# Power_Supply_and_Connector.net
KiCad netlist of a schematic drawn in Altium Designer
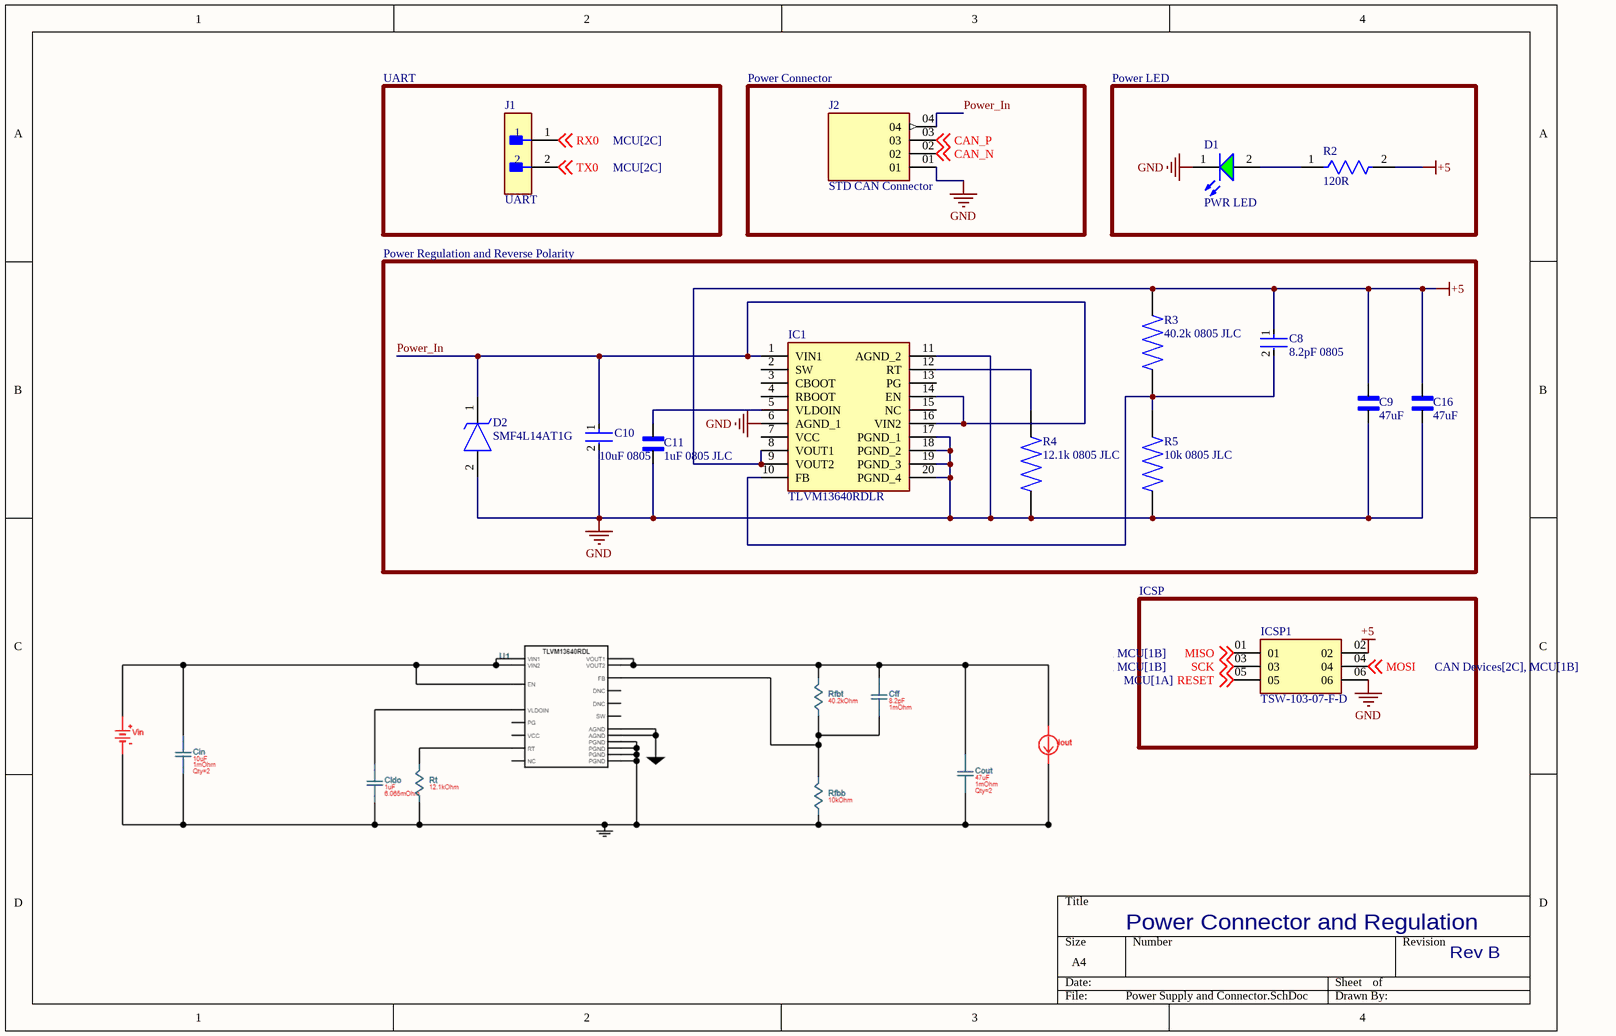
[diagram p0: Power Supply and Connector.SchDoc]

(export (version "E")
  (design (tool "Eeschema 10.0.6"))
  (components
    (comp (ref "C8")
      (value "8.2pF 0805")
      (footprint "FP-GQM219-0_15-IPC_C")
      (description "Ceramic Capacitor 8.2pF ±0.25pF 250VDC C0G 0805 Paper T/R")
      (libsource (lib "Altium Content Vault") (part "b4654b650e69147ec39a6b967a45e02"))
    )
    (comp (ref "C9")
      (value "47uF")
      (footprint "GRM31CR61E476ME44K:CAPC3216X160N")
      (fields
        (field (name "MF") "{'manufacturer': u'Murata Electronics'}")
        (field (name "MP") "GRM31CR61E476ME44K")
      )
      (libsource (lib "*") (part "GRM31CR61E476ME44K"))
    )
    (comp (ref "C10")
      (value "10uF 0805")
      (footprint "FP-GRM21B-0_2-e0_2_0_7-IPC_A")
      (description "Chip Multilayer Ceramic Capacitors for General Purpose, 0805, 10uF, X5R, 15%, 10%, 50V")
      (fields (field (name "TOLERANCE") "10%"))
      (libsource (lib "Altium Content Vault") (part "b4654b650e69147ec39a6b967a45e02"))
    )
    (comp (ref "C11")
      (value "1uF 0805 JLC")
      (footprint "CL21B105KBFNNNE:CAPC2012X140N")
      (description "Capacitor: ceramic; MLCC; 1uF; 50V; X7R; Â±10%; SMD; 0805")
      (fields
        (field (name "MF") "{'manufacturer': u'Samsung Electro-Mechanics'}")
        (field (name "MP") "CL21B105KBFNNNE")
      )
      (libsource (lib "*") (part "CL21B105KBFNNNE"))
    )
    (comp (ref "C16")
      (value "47uF")
      (footprint "GRM31CR61E476ME44K:CAPC3216X160N")
      (fields
        (field (name "MF") "{'manufacturer': u'Murata Electronics'}")
        (field (name "MP") "GRM31CR61E476ME44K")
      )
      (libsource (lib "*") (part "GRM31CR61E476ME44K"))
    )
    (comp (ref "D1")
      (value "PWR LED")
      (footprint "WL-SMCW_0805_150080xx75000")
      (description "WURTH ELEKTRONIK - 150080GS75000 - LED, Green, SMD, 0805, 30 mA, 3.2 V, 520 nm")
      (libsource (lib "Altium Content Vault") (part "LED_Green_2A-1K"))
    )
    (comp (ref "D2")
      (value "SMF4L14AT1G")
      (footprint "SamacSys:SODFL3619X98N")
      (description "TVS Diode (Uni-directional)")
      (fields (field (name "MOUSER PART NUMBER") "576-SMF4L14AT1G"))
      (libsource (lib "*") (part "SMF4L14AT1G"))
    )
    (comp (ref "IC1")
      (value "TLVM13640RDLR")
      (footprint "SamacSys:TLVM13640RDLR")
      (description "Integrated Circuit")
      (fields (field (name "MOUSER PART NUMBER") "595-TLVM13640RDLR"))
      (libsource (lib "*") (part "TLVM13640RDLR"))
    )
    (comp (ref "ICSP1")
      (value "TSW-103-07-F-D")
      (footprint "TSW-103-07-F-D:SAMTEC_TSW-103-07-F-D")
      (fields (field (name "MF") "{'manufacturer': u'Samtec'}"))
      (libsource (lib "*") (part "TSW-103-07-F-D"))
    )
    (comp (ref "J1")
      (value "UART")
      (footprint "FP-TSW-102-07-F-S-MFG")
      (description "CONN HEADER VERT 2POS 2.54MM")
      (libsource (lib "Altium Content Vault") (part "3bc925449376181038e59eaffc5286c"))
    )
    (comp (ref "J2")
      (value "STD CAN Connector")
      (footprint "TSW-104-07-F-S:SAMTEC_TSW-104-07-F-S")
      (fields (field (name "MF") "{'manufacturer': u'Samtec'}") (field (name "MP") "TSW-104-07-F-S"))
      (libsource (lib "*") (part "TSW-104-07-F-S"))
    )
    (comp (ref "R2")
      (value "120R")
      (footprint "FP-CRCW0805-e3-IPC_C")
      (description "RES Thick Film, 120Ω, 1%, 0.125W, 100ppm/°C, 0805")
      (fields (field (name "TOLERANCE") "1%"))
      (libsource (lib "Altium Content Vault") (part "1029c3af85768c4190bb7ad29bc67b5"))
    )
    (comp (ref "R3")
      (value "40.2k 0805 JLC")
      (footprint "0805W8F4022T5E:RESC2012X65N")
      (fields (field (name "MF") "{'manufacturer': u'Uni-Royal'}") (field (name "MP") "0805W8F4022T5E"))
      (libsource (lib "*") (part "0805W8F4022T5E"))
    )
    (comp (ref "R4")
      (value "12.1k 0805 JLC")
      (footprint "0805W8F1212T5E:RESC2012X65N")
      (fields (field (name "MF") "{'manufacturer': u'Uni-Royal'}") (field (name "MP") "0805W8F1212T5E"))
      (libsource (lib "*") (part "0805W8F1212T5E"))
    )
    (comp (ref "R5")
      (value "10k 0805 JLC")
      (footprint "0805W8F1002T5E:RESC2012X65N")
      (fields (field (name "MF") "{'manufacturer': u'Uni-Royal'}") (field (name "MP") "0805W8F1002T5E"))
      (libsource (lib "*") (part "0805W8F1002T5E"))
    )
  )
  (nets
    (net (code "1") (name "+5") (class "Default")
      (node (ref "C16") (pin "2") (pinfunction "2_2") (pintype "passive"))
      (node (ref "C8") (pin "1") (pinfunction "1_1") (pintype "passive"))
      (node (ref "C9") (pin "2") (pinfunction "2_2") (pintype "passive"))
      (node (ref "IC1") (pin "8") (pinfunction "VOUT1_8") (pintype "passive"))
      (node (ref "IC1") (pin "9") (pinfunction "VOUT2_9") (pintype "passive"))
      (node (ref "ICSP1") (pin "02") (pinfunction "02_02") (pintype "passive"))
      (node (ref "R2") (pin "2") (pinfunction "2_2") (pintype "passive"))
      (node (ref "R3") (pin "2") (pinfunction "2_2") (pintype "passive"))
    )
    (net (code "2") (name "/Power_In") (class "Default")
      (node (ref "C10") (pin "1") (pinfunction "1_1") (pintype "passive"))
      (node (ref "D2") (pin "1") (pinfunction "K_1") (pintype "passive"))
      (node (ref "IC1") (pin "1") (pinfunction "VIN1_1") (pintype "passive"))
      (node (ref "IC1") (pin "14") (pinfunction "EN_14") (pintype "passive"))
      (node (ref "IC1") (pin "16") (pinfunction "VIN2_16") (pintype "passive"))
      (node (ref "J2") (pin "04") (pinfunction "04_04") (pintype "output"))
    )
    (net (code "3") (name "CAN_N") (class "Default")
      (node (ref "J2") (pin "02") (pinfunction "02_02") (pintype "passive"))
    )
    (net (code "4") (name "CAN_P") (class "Default")
      (node (ref "J2") (pin "03") (pinfunction "03_03") (pintype "passive"))
    )
    (net (code "5") (name "GND") (class "Default")
      (node (ref "C10") (pin "2") (pinfunction "2_2") (pintype "passive"))
      (node (ref "C11") (pin "2") (pinfunction "2_2") (pintype "passive"))
      (node (ref "C16") (pin "1") (pinfunction "1_1") (pintype "passive"))
      (node (ref "C9") (pin "1") (pinfunction "1_1") (pintype "passive"))
      (node (ref "D1") (pin "1") (pinfunction "K_1") (pintype "passive"))
      (node (ref "D2") (pin "2") (pinfunction "A_2") (pintype "passive"))
      (node (ref "IC1") (pin "11") (pinfunction "AGND_2_11") (pintype "passive"))
      (node (ref "IC1") (pin "17") (pinfunction "PGND_1_17") (pintype "passive"))
      (node (ref "IC1") (pin "18") (pinfunction "PGND_2_18") (pintype "passive"))
      (node (ref "IC1") (pin "19") (pinfunction "PGND_3_19") (pintype "passive"))
      (node (ref "IC1") (pin "20") (pinfunction "PGND_4_20") (pintype "passive"))
      (node (ref "IC1") (pin "6") (pinfunction "AGND_1_6") (pintype "passive"))
      (node (ref "ICSP1") (pin "06") (pinfunction "06_06") (pintype "passive"))
      (node (ref "J2") (pin "01") (pinfunction "01_01") (pintype "passive"))
      (node (ref "R4") (pin "1") (pinfunction "1_1") (pintype "passive"))
      (node (ref "R5") (pin "1") (pinfunction "1_1") (pintype "passive"))
    )
    (net (code "6") (name "MISO") (class "Default")
      (node (ref "ICSP1") (pin "01") (pinfunction "01_01") (pintype "passive"))
    )
    (net (code "7") (name "MOSI") (class "Default")
      (node (ref "ICSP1") (pin "04") (pinfunction "04_04") (pintype "passive"))
    )
    (net (code "8") (name "Net-(D1-A)") (class "Default")
      (node (ref "D1") (pin "2") (pinfunction "A_2") (pintype "passive"))
      (node (ref "R2") (pin "1") (pinfunction "1_1") (pintype "passive"))
    )
    (net (code "9") (name "Net-(IC1-FB)") (class "Default")
      (node (ref "C8") (pin "2") (pinfunction "2_2") (pintype "passive"))
      (node (ref "IC1") (pin "10") (pinfunction "FB_10") (pintype "passive"))
      (node (ref "R3") (pin "1") (pinfunction "1_1") (pintype "passive"))
      (node (ref "R5") (pin "2") (pinfunction "2_2") (pintype "passive"))
    )
    (net (code "10") (name "Net-(IC1-RT)") (class "Default")
      (node (ref "IC1") (pin "12") (pinfunction "RT_12") (pintype "passive"))
      (node (ref "R4") (pin "2") (pinfunction "2_2") (pintype "passive"))
    )
    (net (code "11") (name "Net-(IC1-VLDOIN)") (class "Default")
      (node (ref "C11") (pin "1") (pinfunction "1_1") (pintype "passive"))
      (node (ref "IC1") (pin "5") (pinfunction "VLDOIN_5") (pintype "passive"))
    )
    (net (code "12") (name "RESET") (class "Default")
      (node (ref "ICSP1") (pin "05") (pinfunction "05_05") (pintype "passive"))
    )
    (net (code "13") (name "RX0") (class "Default")
      (node (ref "J1") (pin "1") (pinfunction "1_1") (pintype "passive"))
    )
    (net (code "14") (name "SCK") (class "Default")
      (node (ref "ICSP1") (pin "03") (pinfunction "03_03") (pintype "passive"))
    )
    (net (code "15") (name "TX0") (class "Default")
      (node (ref "J1") (pin "2") (pinfunction "2_2") (pintype "passive"))
    )
    (net (code "16") (name "unconnected-(IC1-CBOOT-Pad3)") (class "Default")
      (node (ref "IC1") (pin "3") (pinfunction "CBOOT_3") (pintype "passive"))
    )
    (net (code "17") (name "unconnected-(IC1-NC-Pad15)") (class "Default")
      (node (ref "IC1") (pin "15") (pinfunction "NC_15") (pintype "passive"))
    )
    (net (code "18") (name "unconnected-(IC1-PG-Pad13)") (class "Default")
      (node (ref "IC1") (pin "13") (pinfunction "PG_13") (pintype "passive"))
    )
    (net (code "19") (name "unconnected-(IC1-RBOOT-Pad4)") (class "Default")
      (node (ref "IC1") (pin "4") (pinfunction "RBOOT_4") (pintype "passive"))
    )
    (net (code "20") (name "unconnected-(IC1-SW-Pad2)") (class "Default")
      (node (ref "IC1") (pin "2") (pinfunction "SW_2") (pintype "passive"))
    )
    (net (code "21") (name "unconnected-(IC1-VCC-Pad7)") (class "Default")
      (node (ref "IC1") (pin "7") (pinfunction "VCC_7") (pintype "passive"))
    )
  )
)
